# EuclidSeqNano_2020-09-19_19-44-00.net
KiCad netlist of a schematic drawn in EasyEDA
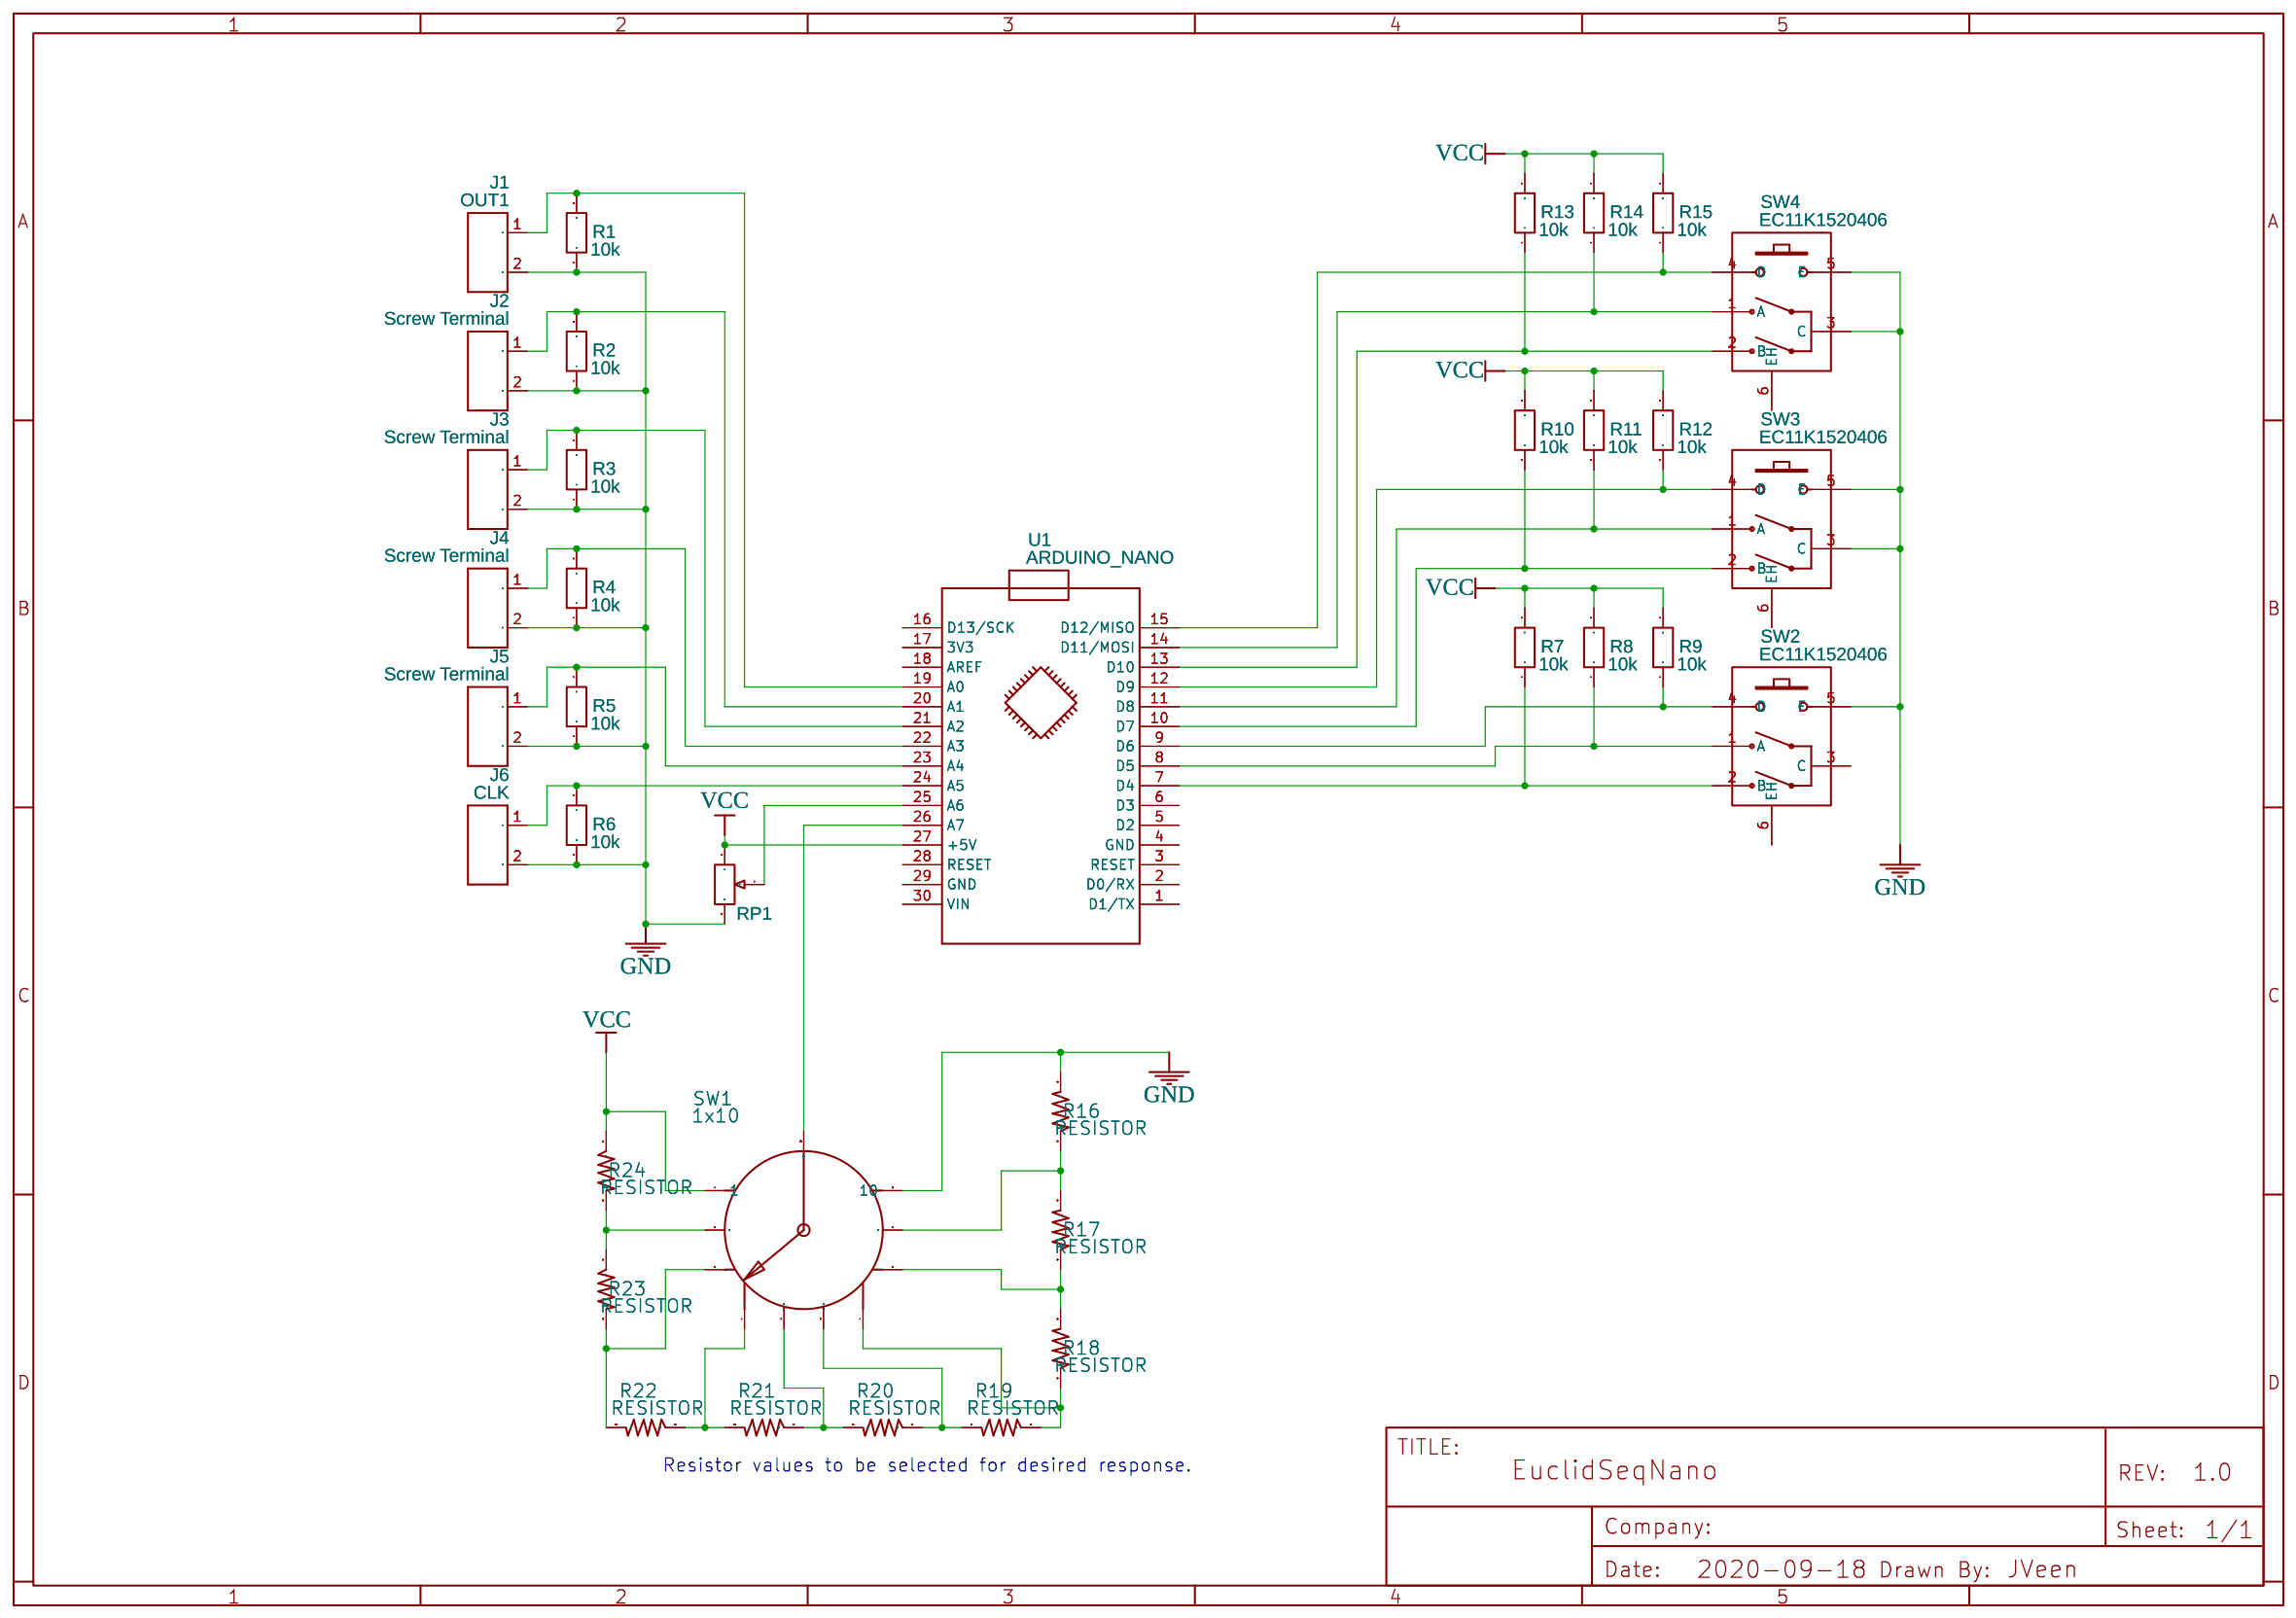
[diagram p0: schematic sheet]

(export (version "E")
  (design (tool "Eeschema 10.0.6"))
  (components
    (comp (ref "J1")
      (value "OUT1")
      (fields (field (name "BOM_Manufacturer Part") "?"))
      (libsource (lib "") (part "Unknown_245_-685"))
    )
    (comp (ref "J2")
      (value "Screw Terminal")
      (fields (field (name "BOM_Manufacturer Part") "?"))
      (libsource (lib "") (part "Unknown_245_-625"))
    )
    (comp (ref "J3")
      (value "Screw Terminal")
      (fields (field (name "BOM_Manufacturer Part") "?"))
      (libsource (lib "") (part "Unknown_245_-565"))
    )
    (comp (ref "J4")
      (value "Screw Terminal")
      (fields (field (name "BOM_Manufacturer Part") "?"))
      (libsource (lib "") (part "Unknown_245_-505"))
    )
    (comp (ref "J5")
      (value "Screw Terminal")
      (fields (field (name "BOM_Manufacturer Part") "?"))
      (libsource (lib "") (part "Unknown_245_-445"))
    )
    (comp (ref "J6")
      (value "CLK")
      (fields (field (name "BOM_Manufacturer Part") "?"))
      (libsource (lib "") (part "Unknown_245_-385"))
    )
    (comp (ref "R1") (value "10k") (libsource (lib "") (part "R_0603_EU")))
    (comp (ref "R2") (value "10k") (libsource (lib "") (part "R_0603_EU")))
    (comp (ref "R3") (value "10k") (libsource (lib "") (part "R_0603_EU")))
    (comp (ref "R4") (value "10k") (libsource (lib "") (part "R_0603_EU")))
    (comp (ref "R5") (value "10k") (libsource (lib "") (part "R_0603_EU")))
    (comp (ref "R6") (value "10k") (libsource (lib "") (part "R_0603_EU")))
    (comp (ref "R7") (value "10k") (libsource (lib "") (part "R_0603_EU")))
    (comp (ref "R8") (value "10k") (libsource (lib "") (part "R_0603_EU")))
    (comp (ref "R9") (value "10k") (libsource (lib "") (part "R_0603_EU")))
    (comp (ref "R10") (value "10k") (libsource (lib "") (part "R_0603_EU")))
    (comp (ref "R11") (value "10k") (libsource (lib "") (part "R_0603_EU")))
    (comp (ref "R12") (value "10k") (libsource (lib "") (part "R_0603_EU")))
    (comp (ref "R13") (value "10k") (libsource (lib "") (part "R_0603_EU")))
    (comp (ref "R14") (value "10k") (libsource (lib "") (part "R_0603_EU")))
    (comp (ref "R15") (value "10k") (libsource (lib "") (part "R_0603_EU")))
    (comp (ref "R16") (value "RESISTOR") (libsource (lib "") (part "Unknown_530_-250")))
    (comp (ref "R17") (value "RESISTOR") (libsource (lib "") (part "Unknown_530_-190")))
    (comp (ref "R18") (value "RESISTOR") (libsource (lib "") (part "Unknown_530_-130")))
    (comp (ref "R19") (value "RESISTOR") (libsource (lib "") (part "Unknown_500_-90")))
    (comp (ref "R20") (value "RESISTOR") (libsource (lib "") (part "Unknown_440_-90")))
    (comp (ref "R21") (value "RESISTOR") (libsource (lib "") (part "Unknown_380_-90")))
    (comp (ref "R22") (value "RESISTOR") (libsource (lib "") (part "Unknown_320_-90")))
    (comp (ref "R23") (value "RESISTOR") (libsource (lib "") (part "Unknown_300_-160")))
    (comp (ref "R24") (value "RESISTOR") (libsource (lib "") (part "Unknown_300_-220")))
    (comp (ref "RP1") (value "R_3386P_EU") (libsource (lib "") (part "R_3386P_EU")))
    (comp (ref "SW1") (value "1x10") (libsource (lib "") (part "Unknown_400_-190")))
    (comp (ref "SW2")
      (value "EC11K1520406")
      (fields (field (name "BOM_Supplier Part") "C470721"))
      (libsource (lib "") (part "EC11K1520406"))
    )
    (comp (ref "SW3")
      (value "EC11K1520406")
      (fields (field (name "BOM_Supplier Part") "C470721"))
      (libsource (lib "") (part "EC11K1520406"))
    )
    (comp (ref "SW4")
      (value "EC11K1520406")
      (fields (field (name "BOM_Supplier Part") "C470721"))
      (libsource (lib "") (part "EC11K1520406"))
    )
    (comp (ref "U1")
      (value "ARDUINO_NANO")
      (fields (field (name "BOM_Manufacturer Part") "?"))
      (libsource (lib "") (part "Unknown_520_-430"))
    )
  )
  (nets
    (net (code "1") (name "GND") (class "Default")
      (node (ref "J1") (pin "2") (pinfunction "2_2") (pintype "unspecified"))
      (node (ref "J2") (pin "2") (pinfunction "2_2") (pintype "unspecified"))
      (node (ref "J3") (pin "2") (pinfunction "2_2") (pintype "unspecified"))
      (node (ref "J4") (pin "2") (pinfunction "2_2") (pintype "unspecified"))
      (node (ref "J5") (pin "2") (pinfunction "2_2") (pintype "unspecified"))
      (node (ref "J6") (pin "2") (pinfunction "2_2") (pintype "unspecified"))
      (node (ref "R1") (pin "1") (pinfunction "1_1") (pintype "unspecified"))
      (node (ref "R16") (pin "P$2") (pinfunction "2_P$2") (pintype "unspecified"))
      (node (ref "R2") (pin "1") (pinfunction "1_1") (pintype "unspecified"))
      (node (ref "R3") (pin "1") (pinfunction "1_1") (pintype "unspecified"))
      (node (ref "R4") (pin "1") (pinfunction "1_1") (pintype "unspecified"))
      (node (ref "R5") (pin "1") (pinfunction "1_1") (pintype "unspecified"))
      (node (ref "R6") (pin "1") (pinfunction "1_1") (pintype "unspecified"))
      (node (ref "RP1") (pin "3") (pinfunction "3_3") (pintype "input"))
      (node (ref "SW1") (pin "10") (pinfunction "10_10") (pintype "unspecified"))
      (node (ref "SW2") (pin "5") (pinfunction "E_5") (pintype "unspecified"))
      (node (ref "SW3") (pin "3") (pinfunction "C_3") (pintype "unspecified"))
      (node (ref "SW3") (pin "5") (pinfunction "E_5") (pintype "unspecified"))
      (node (ref "SW4") (pin "3") (pinfunction "C_3") (pintype "unspecified"))
      (node (ref "SW4") (pin "5") (pinfunction "E_5") (pintype "unspecified"))
    )
    (net (code "2") (name "Net-(R16-1)") (class "Default")
      (node (ref "R16") (pin "P$1") (pinfunction "1_P$1") (pintype "unspecified"))
      (node (ref "R17") (pin "P$2") (pinfunction "2_P$2") (pintype "unspecified"))
      (node (ref "SW1") (pin "9") (pinfunction "9_9") (pintype "unspecified"))
    )
    (net (code "3") (name "Net-(R17-1)") (class "Default")
      (node (ref "R17") (pin "P$1") (pinfunction "1_P$1") (pintype "unspecified"))
      (node (ref "R18") (pin "P$2") (pinfunction "2_P$2") (pintype "unspecified"))
      (node (ref "SW1") (pin "8") (pinfunction "8_8") (pintype "unspecified"))
    )
    (net (code "4") (name "Net-(R18-1)") (class "Default")
      (node (ref "R18") (pin "P$1") (pinfunction "1_P$1") (pintype "unspecified"))
      (node (ref "R19") (pin "P$1") (pinfunction "1_P$1") (pintype "unspecified"))
      (node (ref "SW1") (pin "7") (pinfunction "7_7") (pintype "unspecified"))
    )
    (net (code "5") (name "Net-(R19-2)") (class "Default")
      (node (ref "R19") (pin "P$2") (pinfunction "2_P$2") (pintype "unspecified"))
      (node (ref "R20") (pin "P$1") (pinfunction "1_P$1") (pintype "unspecified"))
      (node (ref "SW1") (pin "6") (pinfunction "6_6") (pintype "unspecified"))
    )
    (net (code "6") (name "Net-(R20-2)") (class "Default")
      (node (ref "R20") (pin "P$2") (pinfunction "2_P$2") (pintype "unspecified"))
      (node (ref "R21") (pin "P$1") (pinfunction "1_P$1") (pintype "unspecified"))
      (node (ref "SW1") (pin "5") (pinfunction "5_5") (pintype "unspecified"))
    )
    (net (code "7") (name "Net-(R21-2)") (class "Default")
      (node (ref "R21") (pin "P$2") (pinfunction "2_P$2") (pintype "unspecified"))
      (node (ref "R22") (pin "P$1") (pinfunction "1_P$1") (pintype "unspecified"))
      (node (ref "SW1") (pin "4") (pinfunction "4_4") (pintype "unspecified"))
    )
    (net (code "8") (name "Net-(R22-2)") (class "Default")
      (node (ref "R22") (pin "P$2") (pinfunction "2_P$2") (pintype "unspecified"))
      (node (ref "R23") (pin "P$2") (pinfunction "2_P$2") (pintype "unspecified"))
      (node (ref "SW1") (pin "3") (pinfunction "3_3") (pintype "unspecified"))
    )
    (net (code "9") (name "Net-(R23-1)") (class "Default")
      (node (ref "R23") (pin "P$1") (pinfunction "1_P$1") (pintype "unspecified"))
      (node (ref "R24") (pin "P$2") (pinfunction "2_P$2") (pintype "unspecified"))
      (node (ref "SW1") (pin "2") (pinfunction "2_2") (pintype "unspecified"))
    )
    (net (code "10") (name "Net-(SW2-A)") (class "Default")
      (node (ref "R8") (pin "1") (pinfunction "1_1") (pintype "unspecified"))
      (node (ref "SW2") (pin "1") (pinfunction "A_1") (pintype "unspecified"))
      (node (ref "U1") (pin "8") (pinfunction "D5_8") (pintype "unspecified"))
    )
    (net (code "11") (name "Net-(SW2-B)") (class "Default")
      (node (ref "R7") (pin "1") (pinfunction "1_1") (pintype "unspecified"))
      (node (ref "SW2") (pin "2") (pinfunction "B_2") (pintype "unspecified"))
      (node (ref "U1") (pin "7") (pinfunction "D4_7") (pintype "unspecified"))
    )
    (net (code "12") (name "Net-(SW2-D)") (class "Default")
      (node (ref "R9") (pin "1") (pinfunction "1_1") (pintype "unspecified"))
      (node (ref "SW2") (pin "4") (pinfunction "D_4") (pintype "unspecified"))
      (node (ref "U1") (pin "9") (pinfunction "D6_9") (pintype "unspecified"))
    )
    (net (code "13") (name "Net-(SW3-A)") (class "Default")
      (node (ref "R11") (pin "1") (pinfunction "1_1") (pintype "unspecified"))
      (node (ref "SW3") (pin "1") (pinfunction "A_1") (pintype "unspecified"))
      (node (ref "U1") (pin "11") (pinfunction "D8_11") (pintype "unspecified"))
    )
    (net (code "14") (name "Net-(SW3-B)") (class "Default")
      (node (ref "R10") (pin "1") (pinfunction "1_1") (pintype "unspecified"))
      (node (ref "SW3") (pin "2") (pinfunction "B_2") (pintype "unspecified"))
      (node (ref "U1") (pin "10") (pinfunction "D7_10") (pintype "unspecified"))
    )
    (net (code "15") (name "Net-(SW3-D)") (class "Default")
      (node (ref "R12") (pin "1") (pinfunction "1_1") (pintype "unspecified"))
      (node (ref "SW3") (pin "4") (pinfunction "D_4") (pintype "unspecified"))
      (node (ref "U1") (pin "12") (pinfunction "D9_12") (pintype "unspecified"))
    )
    (net (code "16") (name "Net-(SW4-A)") (class "Default")
      (node (ref "R14") (pin "1") (pinfunction "1_1") (pintype "unspecified"))
      (node (ref "SW4") (pin "1") (pinfunction "A_1") (pintype "unspecified"))
      (node (ref "U1") (pin "14") (pinfunction "D11/MOSI_14") (pintype "unspecified"))
    )
    (net (code "17") (name "Net-(SW4-B)") (class "Default")
      (node (ref "R13") (pin "1") (pinfunction "1_1") (pintype "unspecified"))
      (node (ref "SW4") (pin "2") (pinfunction "B_2") (pintype "unspecified"))
      (node (ref "U1") (pin "13") (pinfunction "D10_13") (pintype "unspecified"))
    )
    (net (code "18") (name "Net-(SW4-D)") (class "Default")
      (node (ref "R15") (pin "1") (pinfunction "1_1") (pintype "unspecified"))
      (node (ref "SW4") (pin "4") (pinfunction "D_4") (pintype "unspecified"))
      (node (ref "U1") (pin "15") (pinfunction "D12/MISO_15") (pintype "unspecified"))
    )
    (net (code "19") (name "Net-(U1-A0)") (class "Default")
      (node (ref "J1") (pin "1") (pinfunction "1_1") (pintype "unspecified"))
      (node (ref "R1") (pin "2") (pinfunction "2_2") (pintype "unspecified"))
      (node (ref "U1") (pin "19") (pinfunction "A0_19") (pintype "unspecified"))
    )
    (net (code "20") (name "Net-(U1-A1)") (class "Default")
      (node (ref "J2") (pin "1") (pinfunction "1_1") (pintype "unspecified"))
      (node (ref "R2") (pin "2") (pinfunction "2_2") (pintype "unspecified"))
      (node (ref "U1") (pin "20") (pinfunction "A1_20") (pintype "unspecified"))
    )
    (net (code "21") (name "Net-(U1-A2)") (class "Default")
      (node (ref "J3") (pin "1") (pinfunction "1_1") (pintype "unspecified"))
      (node (ref "R3") (pin "2") (pinfunction "2_2") (pintype "unspecified"))
      (node (ref "U1") (pin "21") (pinfunction "A2_21") (pintype "unspecified"))
    )
    (net (code "22") (name "Net-(U1-A3)") (class "Default")
      (node (ref "J4") (pin "1") (pinfunction "1_1") (pintype "unspecified"))
      (node (ref "R4") (pin "2") (pinfunction "2_2") (pintype "unspecified"))
      (node (ref "U1") (pin "22") (pinfunction "A3_22") (pintype "unspecified"))
    )
    (net (code "23") (name "Net-(U1-A4)") (class "Default")
      (node (ref "J5") (pin "1") (pinfunction "1_1") (pintype "unspecified"))
      (node (ref "R5") (pin "2") (pinfunction "2_2") (pintype "unspecified"))
      (node (ref "U1") (pin "23") (pinfunction "A4_23") (pintype "unspecified"))
    )
    (net (code "24") (name "Net-(U1-A5)") (class "Default")
      (node (ref "J6") (pin "1") (pinfunction "1_1") (pintype "unspecified"))
      (node (ref "R6") (pin "2") (pinfunction "2_2") (pintype "unspecified"))
      (node (ref "U1") (pin "24") (pinfunction "A5_24") (pintype "unspecified"))
    )
    (net (code "25") (name "Net-(U1-A6)") (class "Default")
      (node (ref "RP1") (pin "2") (pinfunction "2_2") (pintype "input"))
      (node (ref "U1") (pin "25") (pinfunction "A6_25") (pintype "unspecified"))
    )
    (net (code "26") (name "Net-(U1-A7)") (class "Default")
      (node (ref "SW1") (pin "COMMON") (pinfunction "COMMON_COMMON") (pintype "unspecified"))
      (node (ref "U1") (pin "26") (pinfunction "A7_26") (pintype "unspecified"))
    )
    (net (code "27") (name "VCC") (class "Default")
      (node (ref "R10") (pin "2") (pinfunction "2_2") (pintype "unspecified"))
      (node (ref "R11") (pin "2") (pinfunction "2_2") (pintype "unspecified"))
      (node (ref "R12") (pin "2") (pinfunction "2_2") (pintype "unspecified"))
      (node (ref "R13") (pin "2") (pinfunction "2_2") (pintype "unspecified"))
      (node (ref "R14") (pin "2") (pinfunction "2_2") (pintype "unspecified"))
      (node (ref "R15") (pin "2") (pinfunction "2_2") (pintype "unspecified"))
      (node (ref "R24") (pin "P$1") (pinfunction "1_P$1") (pintype "unspecified"))
      (node (ref "R7") (pin "2") (pinfunction "2_2") (pintype "unspecified"))
      (node (ref "R8") (pin "2") (pinfunction "2_2") (pintype "unspecified"))
      (node (ref "R9") (pin "2") (pinfunction "2_2") (pintype "unspecified"))
      (node (ref "RP1") (pin "1") (pinfunction "1_1") (pintype "input"))
      (node (ref "SW1") (pin "1") (pinfunction "1_1") (pintype "unspecified"))
      (node (ref "U1") (pin "27") (pinfunction "+5V_27") (pintype "unspecified"))
    )
    (net (code "28") (name "unconnected-(SW2-C-Pad3)") (class "Default")
      (node (ref "SW2") (pin "3") (pinfunction "C_3") (pintype "unspecified"))
    )
    (net (code "29") (name "unconnected-(SW2-EH-Pad6)") (class "Default")
      (node (ref "SW2") (pin "6") (pinfunction "EH_6") (pintype "unspecified"))
    )
    (net (code "30") (name "unconnected-(SW3-EH-Pad6)") (class "Default")
      (node (ref "SW3") (pin "6") (pinfunction "EH_6") (pintype "unspecified"))
    )
    (net (code "31") (name "unconnected-(SW4-EH-Pad6)") (class "Default")
      (node (ref "SW4") (pin "6") (pinfunction "EH_6") (pintype "unspecified"))
    )
    (net (code "32") (name "unconnected-(U1-3V3-Pad17)") (class "Default")
      (node (ref "U1") (pin "17") (pinfunction "3V3_17") (pintype "unspecified"))
    )
    (net (code "33") (name "unconnected-(U1-AREF-Pad18)") (class "Default")
      (node (ref "U1") (pin "18") (pinfunction "AREF_18") (pintype "unspecified"))
    )
    (net (code "34") (name "unconnected-(U1-D0{slash}RX-Pad2)") (class "Default")
      (node (ref "U1") (pin "2") (pinfunction "D0/RX_2") (pintype "unspecified"))
    )
    (net (code "35") (name "unconnected-(U1-D1{slash}TX-Pad1)") (class "Default")
      (node (ref "U1") (pin "1") (pinfunction "D1/TX_1") (pintype "unspecified"))
    )
    (net (code "36") (name "unconnected-(U1-D2-Pad5)") (class "Default")
      (node (ref "U1") (pin "5") (pinfunction "D2_5") (pintype "unspecified"))
    )
    (net (code "37") (name "unconnected-(U1-D3-Pad6)") (class "Default")
      (node (ref "U1") (pin "6") (pinfunction "D3_6") (pintype "unspecified"))
    )
    (net (code "38") (name "unconnected-(U1-D13{slash}SCK-Pad16)") (class "Default")
      (node (ref "U1") (pin "16") (pinfunction "D13/SCK_16") (pintype "unspecified"))
    )
    (net (code "39") (name "unconnected-(U1-GND-Pad4)") (class "Default")
      (node (ref "U1") (pin "4") (pinfunction "GND_4") (pintype "unspecified"))
    )
    (net (code "40") (name "unconnected-(U1-GND-Pad29)") (class "Default")
      (node (ref "U1") (pin "29") (pinfunction "GND_29") (pintype "unspecified"))
    )
    (net (code "41") (name "unconnected-(U1-RESET-Pad3)") (class "Default")
      (node (ref "U1") (pin "3") (pinfunction "RESET_3") (pintype "unspecified"))
    )
    (net (code "42") (name "unconnected-(U1-RESET-Pad28)") (class "Default")
      (node (ref "U1") (pin "28") (pinfunction "RESET_28") (pintype "unspecified"))
    )
    (net (code "43") (name "unconnected-(U1-VIN-Pad30)") (class "Default")
      (node (ref "U1") (pin "30") (pinfunction "VIN_30") (pintype "unspecified"))
    )
  )
)
